# Buzzer.net
KiCad netlist of a schematic drawn in Altium Designer
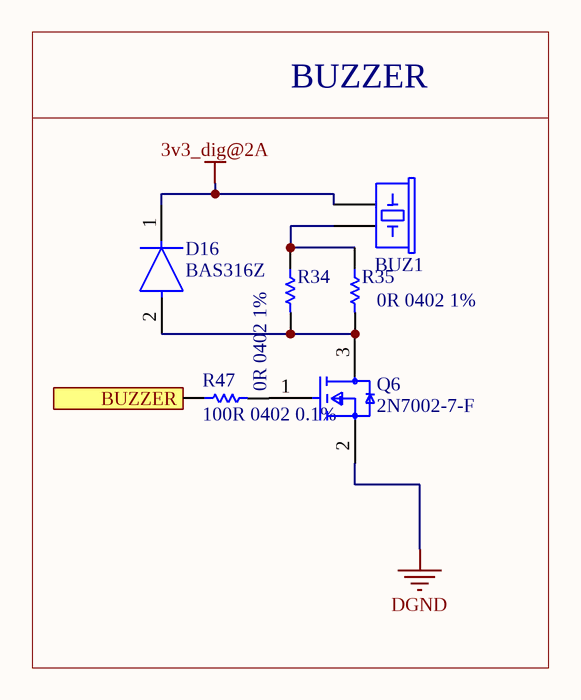
[diagram p0: Buzzer.SchDoc]

(export (version "E")
  (design (tool "Eeschema 10.0.6"))
  (components
    (comp (ref "BUZ1")
      (value "CUI CMT-1285C-035")
      (footprint "BUZZER-12MM-NS")
      (description "Audio Buzzer Magnetic 3Vo-p 5Vo-p 70mA 3.5Vo-p 85dB Through Hole Pin Tray")
      (fields (field (name "MANUFACTURER PART NUMBER") "CMT-1285C-035"))
      (libsource (lib "in3ator") (part "CMP-581a9557be5887dd-1"))
    )
    (comp (ref "D16")
      (value "BAS316Z")
      (footprint "FP-SOD323-IPC_B")
      (description "DIODE GEN PURP 100V 250MA SC76-2")
      (libsource (lib "Altium Content Vault") (part "d7152d700b627762746794eb795d46e"))
    )
    (comp (ref "Q6")
      (value "2N7002-7-F")
      (footprint "FP-SOT23-MFG")
      (description "MOSFET N-CH 60V 115MA SOT23-3")
      (fields (field (name "VOLTAGE") "60V"))
      (libsource (lib "Altium Content Vault") (part "3b9c635fedb024a5347a57b145af9cc"))
    )
    (comp (ref "R34")
      (value "0R 0402 1%")
      (footprint "RESC1005X40X25ML05T10")
      (libsource (lib "Altium Content Vault") (part "RES"))
    )
    (comp (ref "R35")
      (value "0R 0402 1%")
      (footprint "RESC1005X40X25ML05T10")
      (libsource (lib "Altium Content Vault") (part "RES"))
    )
    (comp (ref "R47")
      (value "100R 0402 0.1%")
      (footprint "RESC1005X40X25ML05T10")
      (libsource (lib "Altium Content Vault") (part "RES"))
    )
  )
  (nets
    (net (code "1") (name "/BUZZER") (class "Default")
      (node (ref "R47") (pin "1") (pinfunction "1_1") (pintype "passive"))
    )
    (net (code "2") (name "3v3_dig@2A") (class "Default")
      (node (ref "BUZ1") (pin "1") (pinfunction "+_1") (pintype "passive"))
      (node (ref "D16") (pin "1") (pinfunction "C_1") (pintype "passive"))
    )
    (net (code "3") (name "DGND") (class "Default")
      (node (ref "Q6") (pin "2") (pinfunction "S_2") (pintype "passive"))
    )
    (net (code "4") (name "Net-(BUZ1--)") (class "Default")
      (node (ref "BUZ1") (pin "2") (pinfunction "-_2") (pintype "passive"))
      (node (ref "R34") (pin "1") (pinfunction "1_1") (pintype "passive"))
      (node (ref "R35") (pin "1") (pinfunction "1_1") (pintype "passive"))
    )
    (net (code "5") (name "Net-(D16-A)") (class "Default")
      (node (ref "D16") (pin "2") (pinfunction "A_2") (pintype "passive"))
      (node (ref "Q6") (pin "3") (pinfunction "D_3") (pintype "passive"))
      (node (ref "R34") (pin "2") (pinfunction "2_2") (pintype "passive"))
      (node (ref "R35") (pin "2") (pinfunction "2_2") (pintype "passive"))
    )
    (net (code "6") (name "Net-(Q6-G)") (class "Default")
      (node (ref "Q6") (pin "1") (pinfunction "G_1") (pintype "passive"))
      (node (ref "R47") (pin "2") (pinfunction "2_2") (pintype "passive"))
    )
  )
)
